# MISW_1_3_128x64_OLED.net
KiCad netlist of a schematic drawn in EAGLE
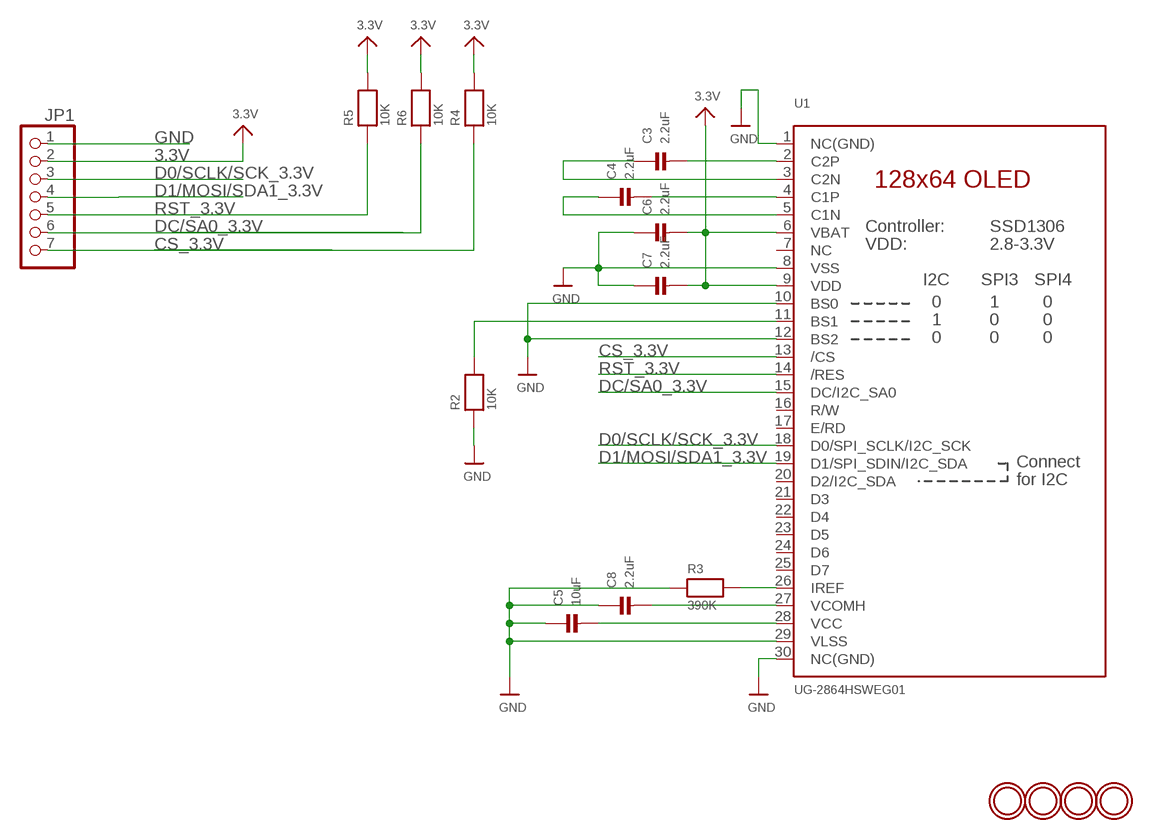
[diagram p0: schematic, sheet 1]

(export (version "E")
  (design (tool "Eeschema 10.0.6"))
  (components
    (comp (ref "C3")
      (value "2.2uF")
      (footprint "eagle-import:0603-MINI")
      (libsource (lib "eagle-import") (part "CAP_CERAMIC0603MINI"))
    )
    (comp (ref "C4")
      (value "2.2uF")
      (footprint "eagle-import:0603-MINI")
      (libsource (lib "eagle-import") (part "CAP_CERAMIC0603MINI"))
    )
    (comp (ref "C5")
      (value "10uF")
      (footprint "eagle-import:0603-MINI")
      (libsource (lib "eagle-import") (part "CAP_CERAMIC0603MINI"))
    )
    (comp (ref "C6")
      (value "2.2uF")
      (footprint "eagle-import:0603-MINI")
      (libsource (lib "eagle-import") (part "CAP_CERAMIC0603MINI"))
    )
    (comp (ref "C7")
      (value "2.2uF")
      (footprint "eagle-import:0603-MINI")
      (libsource (lib "eagle-import") (part "CAP_CERAMIC0603MINI"))
    )
    (comp (ref "C8")
      (value "2.2uF")
      (footprint "eagle-import:0603-MINI")
      (libsource (lib "eagle-import") (part "CAP_CERAMIC0603MINI"))
    )
    (comp (ref "JP1")
      (value "HEADER-1X7ROUND")
      (footprint "eagle-import:1X07_ROUND")
      (libsource (lib "eagle-import") (part "HEADER-1X7ROUND"))
    )
    (comp (ref "R2")
      (value "10K")
      (footprint "eagle-import:0603-MINI")
      (libsource (lib "eagle-import") (part "RESISTOR0603MINI"))
    )
    (comp (ref "R3")
      (value "390K")
      (footprint "eagle-import:0603-MINI")
      (libsource (lib "eagle-import") (part "RESISTOR0603MINI"))
    )
    (comp (ref "R4")
      (value "10K")
      (footprint "eagle-import:0603-MINI")
      (libsource (lib "eagle-import") (part "RESISTOR0603MINI"))
    )
    (comp (ref "R5")
      (value "10K")
      (footprint "eagle-import:0603-MINI")
      (libsource (lib "eagle-import") (part "RESISTOR0603MINI"))
    )
    (comp (ref "R6")
      (value "10K")
      (footprint "eagle-import:0603-MINI")
      (libsource (lib "eagle-import") (part "RESISTOR0603MINI"))
    )
    (comp (ref "U$23")
      (value "MOUNTINGHOLE2.5")
      (footprint "eagle-import:MOUNTINGHOLE_2.5_PLATED")
      (libsource (lib "eagle-import") (part "MOUNTINGHOLE2.5"))
    )
    (comp (ref "U$24")
      (value "MOUNTINGHOLE2.5")
      (footprint "eagle-import:MOUNTINGHOLE_2.5_PLATED")
      (libsource (lib "eagle-import") (part "MOUNTINGHOLE2.5"))
    )
    (comp (ref "U$25")
      (value "MOUNTINGHOLE2.5")
      (footprint "eagle-import:MOUNTINGHOLE_2.5_PLATED")
      (libsource (lib "eagle-import") (part "MOUNTINGHOLE2.5"))
    )
    (comp (ref "U$26")
      (value "MOUNTINGHOLE2.5")
      (footprint "eagle-import:MOUNTINGHOLE_2.5_PLATED")
      (libsource (lib "eagle-import") (part "MOUNTINGHOLE2.5"))
    )
    (comp (ref "U1")
      (value "UG-2864HSWEG01")
      (footprint "eagle-import:UG-2864HSWEG01_1.3_WRAPAROUND")
      (libsource (lib "eagle-import") (part "DISP_OLED_UG-2864HSWEG01"))
    )
  )
  (nets
    (net (code "1") (name "/CS_3.3V") (class "Default")
      (node (ref "JP1") (pin "7") (pinfunction "7_7") (pintype "passive"))
      (node (ref "R4") (pin "1") (pinfunction "1_1") (pintype "passive"))
      (node (ref "U1") (pin "13") (pinfunction "/CS_13") (pintype "input"))
    )
    (net (code "2") (name "/D0{slash}SCLK{slash}SCK_3.3V") (class "Default")
      (node (ref "JP1") (pin "3") (pinfunction "3_3") (pintype "passive"))
      (node (ref "U1") (pin "18") (pinfunction "D0/SPI_SCLK/I2C_SCK_18") (pintype "bidirectional"))
    )
    (net (code "3") (name "/D1{slash}MOSI{slash}SDA1_3.3V") (class "Default")
      (node (ref "JP1") (pin "4") (pinfunction "4_4") (pintype "passive"))
      (node (ref "U1") (pin "19") (pinfunction "D1/SPI_SDIN/I2C_SDA_19") (pintype "bidirectional"))
    )
    (net (code "4") (name "/DC{slash}SA0_3.3V") (class "Default")
      (node (ref "JP1") (pin "6") (pinfunction "6_6") (pintype "passive"))
      (node (ref "R6") (pin "1") (pinfunction "1_1") (pintype "passive"))
      (node (ref "U1") (pin "15") (pinfunction "DC/I2C_SA0_15") (pintype "input"))
    )
    (net (code "5") (name "/RST_3.3V") (class "Default")
      (node (ref "JP1") (pin "5") (pinfunction "5_5") (pintype "passive"))
      (node (ref "R5") (pin "1") (pinfunction "1_1") (pintype "passive"))
      (node (ref "U1") (pin "14") (pinfunction "/RES_14") (pintype "input"))
    )
    (net (code "6") (name "3.3V") (class "Default")
      (node (ref "C6") (pin "2") (pinfunction "P$2_2") (pintype "passive"))
      (node (ref "C7") (pin "2") (pinfunction "P$2_2") (pintype "passive"))
      (node (ref "JP1") (pin "2") (pinfunction "2_2") (pintype "passive"))
      (node (ref "R4") (pin "2") (pinfunction "2_2") (pintype "passive"))
      (node (ref "R5") (pin "2") (pinfunction "2_2") (pintype "passive"))
      (node (ref "R6") (pin "2") (pinfunction "2_2") (pintype "passive"))
      (node (ref "U1") (pin "6") (pinfunction "VBAT_6") (pintype "input"))
      (node (ref "U1") (pin "9") (pinfunction "VDD_9") (pintype "power_in"))
    )
    (net (code "7") (name "GND") (class "Default")
      (node (ref "C5") (pin "1") (pinfunction "P$1_1") (pintype "passive"))
      (node (ref "C6") (pin "1") (pinfunction "P$1_1") (pintype "passive"))
      (node (ref "C7") (pin "1") (pinfunction "P$1_1") (pintype "passive"))
      (node (ref "C8") (pin "1") (pinfunction "P$1_1") (pintype "passive"))
      (node (ref "JP1") (pin "1") (pinfunction "1_1") (pintype "passive"))
      (node (ref "R2") (pin "1") (pinfunction "1_1") (pintype "passive"))
      (node (ref "R3") (pin "1") (pinfunction "1_1") (pintype "passive"))
      (node (ref "U1") (pin "1") (pinfunction "NC(GND)_1") (pintype "input"))
      (node (ref "U1") (pin "10") (pinfunction "BS0_10") (pintype "input"))
      (node (ref "U1") (pin "12") (pinfunction "BS2_12") (pintype "input"))
      (node (ref "U1") (pin "29") (pinfunction "VLSS_29") (pintype "power_in"))
      (node (ref "U1") (pin "30") (pinfunction "NC(GND)_30") (pintype "input"))
      (node (ref "U1") (pin "8") (pinfunction "VSS_8") (pintype "power_in"))
    )
    (net (code "8") (name "Net-(C3-P$1)") (class "Default")
      (node (ref "C3") (pin "1") (pinfunction "P$1_1") (pintype "passive"))
      (node (ref "U1") (pin "3") (pinfunction "C2N_3") (pintype "input"))
    )
    (net (code "9") (name "Net-(C3-P$2)") (class "Default")
      (node (ref "C3") (pin "2") (pinfunction "P$2_2") (pintype "passive"))
      (node (ref "U1") (pin "2") (pinfunction "C2P_2") (pintype "input"))
    )
    (net (code "10") (name "Net-(C4-P$1)") (class "Default")
      (node (ref "C4") (pin "1") (pinfunction "P$1_1") (pintype "passive"))
      (node (ref "U1") (pin "5") (pinfunction "C1N_5") (pintype "input"))
    )
    (net (code "11") (name "Net-(C4-P$2)") (class "Default")
      (node (ref "C4") (pin "2") (pinfunction "P$2_2") (pintype "passive"))
      (node (ref "U1") (pin "4") (pinfunction "C1P_4") (pintype "input"))
    )
    (net (code "12") (name "Net-(C5-P$2)") (class "Default")
      (node (ref "C5") (pin "2") (pinfunction "P$2_2") (pintype "passive"))
      (node (ref "U1") (pin "28") (pinfunction "VCC_28") (pintype "power_in"))
    )
    (net (code "13") (name "Net-(C8-P$2)") (class "Default")
      (node (ref "C8") (pin "2") (pinfunction "P$2_2") (pintype "passive"))
      (node (ref "U1") (pin "27") (pinfunction "VCOMH_27") (pintype "output"))
    )
    (net (code "14") (name "Net-(U1-BS1)") (class "Default")
      (node (ref "R2") (pin "2") (pinfunction "2_2") (pintype "passive"))
      (node (ref "U1") (pin "11") (pinfunction "BS1_11") (pintype "input"))
    )
    (net (code "15") (name "Net-(U1-IREF)") (class "Default")
      (node (ref "R3") (pin "2") (pinfunction "2_2") (pintype "passive"))
      (node (ref "U1") (pin "26") (pinfunction "IREF_26") (pintype "input"))
    )
    (net (code "16") (name "unconnected-(U1-D2{slash}I2C_SDA-Pad20)") (class "Default")
      (node (ref "U1") (pin "20") (pinfunction "D2/I2C_SDA_20") (pintype "bidirectional"))
    )
    (net (code "17") (name "unconnected-(U1-D3-Pad21)") (class "Default")
      (node (ref "U1") (pin "21") (pinfunction "D3_21") (pintype "bidirectional"))
    )
    (net (code "18") (name "unconnected-(U1-D4-Pad22)") (class "Default")
      (node (ref "U1") (pin "22") (pinfunction "D4_22") (pintype "bidirectional"))
    )
    (net (code "19") (name "unconnected-(U1-D5-Pad23)") (class "Default")
      (node (ref "U1") (pin "23") (pinfunction "D5_23") (pintype "bidirectional"))
    )
    (net (code "20") (name "unconnected-(U1-D6-Pad24)") (class "Default")
      (node (ref "U1") (pin "24") (pinfunction "D6_24") (pintype "bidirectional"))
    )
    (net (code "21") (name "unconnected-(U1-D7-Pad25)") (class "Default")
      (node (ref "U1") (pin "25") (pinfunction "D7_25") (pintype "bidirectional"))
    )
    (net (code "22") (name "unconnected-(U1-E{slash}RD-Pad17)") (class "Default")
      (node (ref "U1") (pin "17") (pinfunction "E/RD_17") (pintype "input"))
    )
    (net (code "23") (name "unconnected-(U1-NC-Pad7)") (class "Default")
      (node (ref "U1") (pin "7") (pinfunction "NC_7") (pintype "no_connect"))
    )
    (net (code "24") (name "unconnected-(U1-R{slash}W-Pad16)") (class "Default")
      (node (ref "U1") (pin "16") (pinfunction "R/W_16") (pintype "input"))
    )
  )
)
